# m1k-minus-5-generator.net
KiCad netlist of a schematic drawn in EAGLE
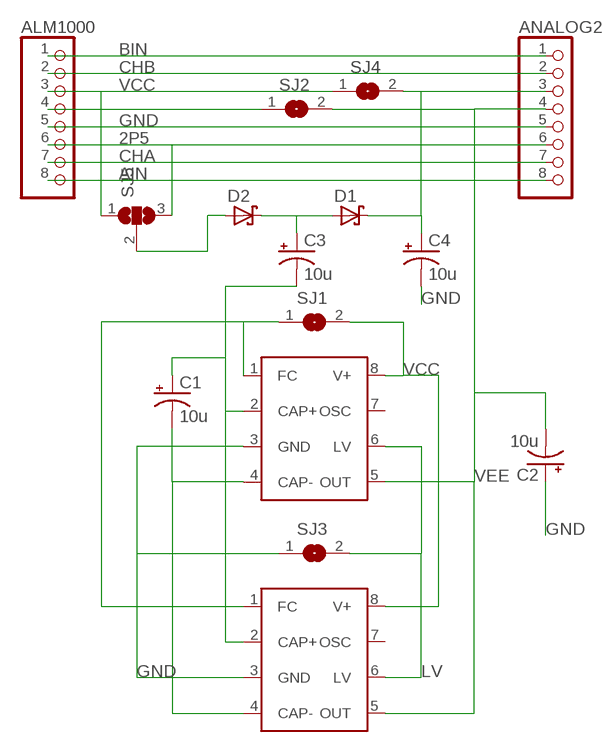
[diagram p0: schematic, sheet 1]

(export (version "E")
  (design (tool "Eeschema 10.0.6"))
  (components
    (comp (ref "ALM1000")
      (value "PINHD-1X8")
      (footprint "eagle-import:1X08")
      (libsource (lib "eagle-import") (part "PINHD-1X8"))
    )
    (comp (ref "ANALOG2")
      (value "PINHD-1X8")
      (footprint "eagle-import:1X08")
      (libsource (lib "eagle-import") (part "PINHD-1X8"))
    )
    (comp (ref "C1")
      (value "10u")
      (footprint "eagle-import:E2,5-6E")
      (libsource (lib "eagle-import") (part "CPOL-USE2,5-6E"))
    )
    (comp (ref "C2")
      (value "10u")
      (footprint "eagle-import:E2,5-6E")
      (libsource (lib "eagle-import") (part "CPOL-USE2,5-6E"))
    )
    (comp (ref "C3")
      (value "10u")
      (footprint "eagle-import:E2,5-6E")
      (libsource (lib "eagle-import") (part "CPOL-USE2,5-6E"))
    )
    (comp (ref "C4")
      (value "10u")
      (footprint "eagle-import:E2,5-6E")
      (libsource (lib "eagle-import") (part "CPOL-USE2,5-6E"))
    )
    (comp (ref "D1")
      (value "SCHOTTKY-DIODEDO35-7")
      (footprint "eagle-import:DO35-7")
      (libsource (lib "eagle-import") (part "SCHOTTKY-DIODEDO35-7"))
    )
    (comp (ref "D2")
      (value "SCHOTTKY-DIODEDO35-7")
      (footprint "eagle-import:DO35-7")
      (libsource (lib "eagle-import") (part "SCHOTTKY-DIODEDO35-7"))
    )
    (comp (ref "SJ1") (value "SJ") (footprint "eagle-import:SJ") (libsource (lib "eagle-import") (part "SJ")))
    (comp (ref "SJ2") (value "SJ") (footprint "eagle-import:SJ") (libsource (lib "eagle-import") (part "SJ")))
    (comp (ref "SJ3") (value "SJ") (footprint "eagle-import:SJ") (libsource (lib "eagle-import") (part "SJ")))
    (comp (ref "SJ4") (value "SJ") (footprint "eagle-import:SJ") (libsource (lib "eagle-import") (part "SJ")))
    (comp (ref "SJ5")
      (value "SJ2W")
      (footprint "eagle-import:SJ_2")
      (libsource (lib "eagle-import") (part "SJ2W"))
    )
    (comp (ref "U1")
      (value "ADM660")
      (footprint "eagle-import:SO8")
      (libsource (lib "eagle-import") (part "ADM660"))
    )
    (comp (ref "U2")
      (value "ADM660DIP")
      (footprint "eagle-import:DIL8")
      (libsource (lib "eagle-import") (part "ADM660DIP"))
    )
  )
  (nets
    (net (code "1") (name "/2P5") (class "Default")
      (node (ref "ALM1000") (pin "6") (pinfunction "6_6") (pintype "passive"))
      (node (ref "ANALOG2") (pin "6") (pinfunction "6_6") (pintype "passive"))
      (node (ref "SJ5") (pin "3") (pinfunction "3_3") (pintype "passive"))
    )
    (net (code "2") (name "/AIN") (class "Default")
      (node (ref "ALM1000") (pin "8") (pinfunction "8_8") (pintype "passive"))
      (node (ref "ANALOG2") (pin "8") (pinfunction "8_8") (pintype "passive"))
    )
    (net (code "3") (name "/BIN") (class "Default")
      (node (ref "ALM1000") (pin "1") (pinfunction "1_1") (pintype "passive"))
      (node (ref "ANALOG2") (pin "1") (pinfunction "1_1") (pintype "passive"))
    )
    (net (code "4") (name "/CHA") (class "Default")
      (node (ref "ALM1000") (pin "7") (pinfunction "7_7") (pintype "passive"))
      (node (ref "ANALOG2") (pin "7") (pinfunction "7_7") (pintype "passive"))
    )
    (net (code "5") (name "/CHB") (class "Default")
      (node (ref "ALM1000") (pin "2") (pinfunction "2_2") (pintype "passive"))
      (node (ref "ANALOG2") (pin "2") (pinfunction "2_2") (pintype "passive"))
    )
    (net (code "6") (name "/GND") (class "Default")
      (node (ref "ALM1000") (pin "5") (pinfunction "5_5") (pintype "passive"))
      (node (ref "ANALOG2") (pin "5") (pinfunction "5_5") (pintype "passive"))
      (node (ref "C2") (pin "+") (pinfunction "+_+") (pintype "passive"))
      (node (ref "C4") (pin "-") (pinfunction "-_-") (pintype "passive"))
      (node (ref "SJ3") (pin "1") (pinfunction "1_1") (pintype "passive"))
      (node (ref "U1") (pin "3") (pinfunction "GND_3") (pintype "bidirectional"))
      (node (ref "U2") (pin "3") (pinfunction "GND_3") (pintype "bidirectional"))
    )
    (net (code "7") (name "/LV") (class "Default")
      (node (ref "SJ3") (pin "2") (pinfunction "2_2") (pintype "passive"))
      (node (ref "U1") (pin "6") (pinfunction "LV_6") (pintype "bidirectional"))
      (node (ref "U2") (pin "6") (pinfunction "LV_6") (pintype "bidirectional"))
    )
    (net (code "8") (name "/VCC") (class "Default")
      (node (ref "ALM1000") (pin "3") (pinfunction "3_3") (pintype "passive"))
      (node (ref "SJ1") (pin "2") (pinfunction "2_2") (pintype "passive"))
      (node (ref "SJ4") (pin "1") (pinfunction "1_1") (pintype "passive"))
      (node (ref "SJ5") (pin "1") (pinfunction "1_1") (pintype "passive"))
      (node (ref "U1") (pin "8") (pinfunction "V+_8") (pintype "bidirectional"))
      (node (ref "U2") (pin "8") (pinfunction "V+_8") (pintype "bidirectional"))
    )
    (net (code "9") (name "/VEE") (class "Default")
      (node (ref "ANALOG2") (pin "4") (pinfunction "4_4") (pintype "passive"))
      (node (ref "C2") (pin "-") (pinfunction "-_-") (pintype "passive"))
      (node (ref "SJ2") (pin "2") (pinfunction "2_2") (pintype "passive"))
      (node (ref "U1") (pin "5") (pinfunction "OUT_5") (pintype "bidirectional"))
      (node (ref "U2") (pin "5") (pinfunction "OUT_5") (pintype "bidirectional"))
    )
    (net (code "10") (name "Net-(ALM1000-Pad4)") (class "Default")
      (node (ref "ALM1000") (pin "4") (pinfunction "4_4") (pintype "passive"))
      (node (ref "SJ2") (pin "1") (pinfunction "1_1") (pintype "passive"))
    )
    (net (code "11") (name "Net-(ANALOG2-Pad3)") (class "Default")
      (node (ref "ANALOG2") (pin "3") (pinfunction "3_3") (pintype "passive"))
      (node (ref "C4") (pin "+") (pinfunction "+_+") (pintype "passive"))
      (node (ref "D1") (pin "C") (pinfunction "C_C") (pintype "passive"))
      (node (ref "SJ4") (pin "2") (pinfunction "2_2") (pintype "passive"))
    )
    (net (code "12") (name "Net-(C3-Pad+)") (class "Default")
      (node (ref "C3") (pin "+") (pinfunction "+_+") (pintype "passive"))
      (node (ref "D1") (pin "A") (pinfunction "A_A") (pintype "passive"))
      (node (ref "D2") (pin "C") (pinfunction "C_C") (pintype "passive"))
    )
    (net (code "13") (name "Net-(D2-PadA)") (class "Default")
      (node (ref "D2") (pin "A") (pinfunction "A_A") (pintype "passive"))
      (node (ref "SJ5") (pin "2") (pinfunction "2_2") (pintype "passive"))
    )
    (net (code "14") (name "Net-(U1-CAP+)") (class "Default")
      (node (ref "C1") (pin "+") (pinfunction "+_+") (pintype "passive"))
      (node (ref "C3") (pin "-") (pinfunction "-_-") (pintype "passive"))
      (node (ref "U1") (pin "2") (pinfunction "CAP+_2") (pintype "bidirectional"))
      (node (ref "U2") (pin "2") (pinfunction "CAP+_2") (pintype "bidirectional"))
    )
    (net (code "15") (name "Net-(U1-CAP-)") (class "Default")
      (node (ref "C1") (pin "-") (pinfunction "-_-") (pintype "passive"))
      (node (ref "U1") (pin "4") (pinfunction "CAP-_4") (pintype "bidirectional"))
      (node (ref "U2") (pin "4") (pinfunction "CAP-_4") (pintype "bidirectional"))
    )
    (net (code "16") (name "Net-(U1-FC)") (class "Default")
      (node (ref "SJ1") (pin "1") (pinfunction "1_1") (pintype "passive"))
      (node (ref "U1") (pin "1") (pinfunction "FC_1") (pintype "bidirectional"))
      (node (ref "U2") (pin "1") (pinfunction "FC_1") (pintype "bidirectional"))
    )
    (net (code "17") (name "unconnected-(U1-OSC-Pad7)") (class "Default")
      (node (ref "U1") (pin "7") (pinfunction "OSC_7") (pintype "bidirectional"))
    )
    (net (code "18") (name "unconnected-(U2-OSC-Pad7)") (class "Default")
      (node (ref "U2") (pin "7") (pinfunction "OSC_7") (pintype "bidirectional"))
    )
  )
)
